# CAN-MPU.net
KiCad netlist of a schematic drawn in EAGLE
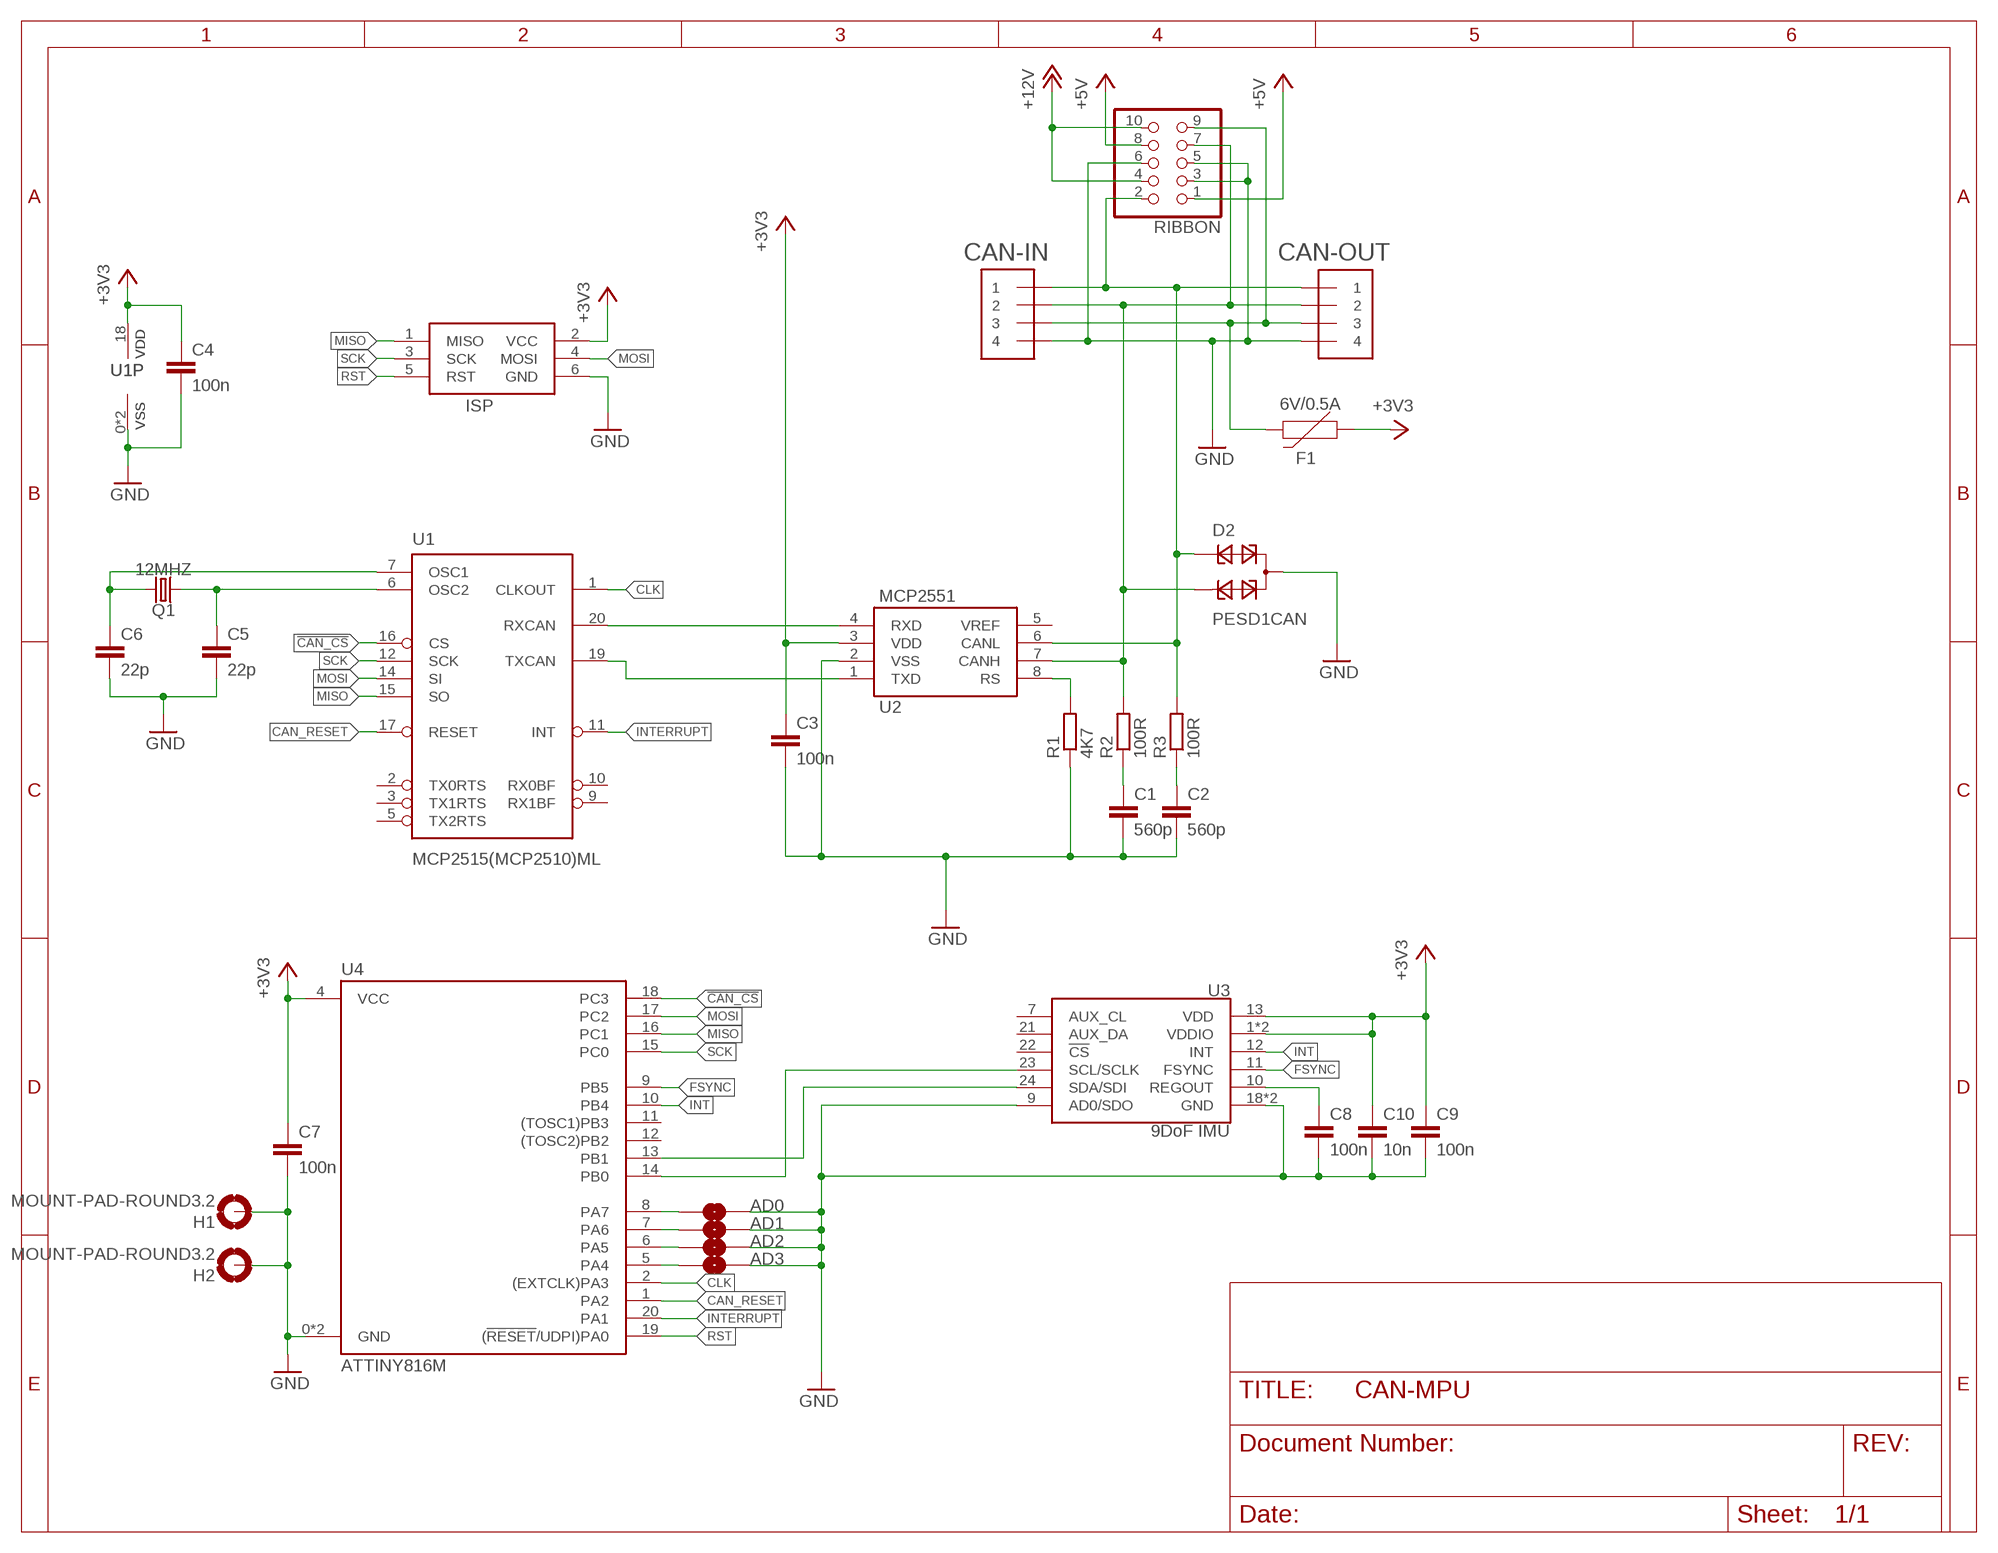
[diagram p0: schematic, sheet 1]

(export (version "E")
  (design (tool "Eeschema 10.0.6"))
  (components
    (comp (ref "AD0")
      (value "JUMPER-SMT_2_NO_SILK")
      (footprint "eagle-import:SMT-JUMPER_2_NO_SILK")
      (libsource (lib "eagle-import") (part "JUMPER-SMT_2_NO_SILK"))
    )
    (comp (ref "AD1")
      (value "JUMPER-SMT_2_NO_SILK")
      (footprint "eagle-import:SMT-JUMPER_2_NO_SILK")
      (libsource (lib "eagle-import") (part "JUMPER-SMT_2_NO_SILK"))
    )
    (comp (ref "AD2")
      (value "JUMPER-SMT_2_NO_SILK")
      (footprint "eagle-import:SMT-JUMPER_2_NO_SILK")
      (libsource (lib "eagle-import") (part "JUMPER-SMT_2_NO_SILK"))
    )
    (comp (ref "AD3")
      (value "JUMPER-SMT_2_NO_SILK")
      (footprint "eagle-import:SMT-JUMPER_2_NO_SILK")
      (libsource (lib "eagle-import") (part "JUMPER-SMT_2_NO_SILK"))
    )
    (comp (ref "C1")
      (value "560p")
      (footprint "eagle-import:C0603")
      (libsource (lib "eagle-import") (part "C-EUC0603"))
    )
    (comp (ref "C2")
      (value "560p")
      (footprint "eagle-import:C0603")
      (libsource (lib "eagle-import") (part "C-EUC0603"))
    )
    (comp (ref "C3")
      (value "100n")
      (footprint "eagle-import:C0603")
      (libsource (lib "eagle-import") (part "C-EUC0603"))
    )
    (comp (ref "C4")
      (value "100n")
      (footprint "eagle-import:C0603")
      (libsource (lib "eagle-import") (part "C-EUC0603"))
    )
    (comp (ref "C5")
      (value "22p")
      (footprint "eagle-import:C0603")
      (libsource (lib "eagle-import") (part "C-EUC0603"))
    )
    (comp (ref "C6")
      (value "22p")
      (footprint "eagle-import:C0603")
      (libsource (lib "eagle-import") (part "C-EUC0603"))
    )
    (comp (ref "C7")
      (value "100n")
      (footprint "eagle-import:C0603")
      (libsource (lib "eagle-import") (part "C-EUC0603"))
    )
    (comp (ref "C8")
      (value "100n")
      (footprint "eagle-import:C0603")
      (libsource (lib "eagle-import") (part "C-EUC0603"))
    )
    (comp (ref "C9")
      (value "100n")
      (footprint "eagle-import:C0603")
      (libsource (lib "eagle-import") (part "C-EUC0603"))
    )
    (comp (ref "C10")
      (value "10n")
      (footprint "eagle-import:C0603")
      (libsource (lib "eagle-import") (part "C-EUC0603"))
    )
    (comp (ref "CAN-IN")
      (value "STRAWSON_EAGLE_LIB_JST_SH_4")
      (footprint "eagle-import:STRAWSON_EAGLE_LIB_JST_SH_4_SMD")
      (libsource (lib "eagle-import") (part "STRAWSON_EAGLE_LIB_JST_SH_4"))
    )
    (comp (ref "CAN-OUT")
      (value "STRAWSON_EAGLE_LIB_JST_SH_4")
      (footprint "eagle-import:STRAWSON_EAGLE_LIB_JST_SH_4_SMD")
      (libsource (lib "eagle-import") (part "STRAWSON_EAGLE_LIB_JST_SH_4"))
    )
    (comp (ref "D2")
      (value "PESD1CAN")
      (footprint "eagle-import:SOT23")
      (libsource (lib "eagle-import") (part "PESD1CAN"))
    )
    (comp (ref "F1")
      (value "6V/0.5A")
      (footprint "eagle-import:1206")
      (libsource (lib "eagle-import") (part "PPTC_HALF-AMP"))
    )
    (comp (ref "H1")
      (value "MOUNT-PAD-ROUND3.2")
      (footprint "eagle-import:3,2-PAD")
      (libsource (lib "eagle-import") (part "MOUNT-PAD-ROUND3.2"))
    )
    (comp (ref "H2")
      (value "MOUNT-PAD-ROUND3.2")
      (footprint "eagle-import:3,2-PAD")
      (libsource (lib "eagle-import") (part "MOUNT-PAD-ROUND3.2"))
    )
    (comp (ref "ISP")
      (value "AVRISP-6")
      (footprint "eagle-import:AVRISP")
      (libsource (lib "eagle-import") (part "AVRISP-6"))
    )
    (comp (ref "Q1")
      (value "12MHZ")
      (footprint "eagle-import:CRYSTAL-SMD-3.2X1.5MM")
      (libsource (lib "eagle-import") (part "CRYSTALSMD-3.2X1.5"))
    )
    (comp (ref "R1")
      (value "4K7")
      (footprint "eagle-import:R0603")
      (libsource (lib "eagle-import") (part "R-EU_R0603"))
    )
    (comp (ref "R2")
      (value "100R")
      (footprint "eagle-import:R0603")
      (libsource (lib "eagle-import") (part "R-EU_R0603"))
    )
    (comp (ref "R3")
      (value "100R")
      (footprint "eagle-import:R0603")
      (libsource (lib "eagle-import") (part "R-EU_R0603"))
    )
    (comp (ref "RIBBON")
      (value "PINHD-2X5_2.54-SMD")
      (footprint "eagle-import:2X05SMD")
      (libsource (lib "eagle-import") (part "PINHD-2X5_2.54-SMD"))
    )
    (comp (ref "U1")
      (value "MCP2515(MCP2510)ML")
      (footprint "eagle-import:QFN20")
      (libsource (lib "eagle-import") (part "MCP2515(MCP2510)ML"))
    )
    (comp (ref "U2")
      (value "MCP2551")
      (footprint "eagle-import:SO08")
      (libsource (lib "eagle-import") (part "MCP2551"))
    )
    (comp (ref "U3")
      (value "9DoF IMU")
      (footprint "eagle-import:QFN24-3X3")
      (libsource (lib "eagle-import") (part "MPU-9250"))
    )
    (comp (ref "U4")
      (value "ATTINY816M")
      (footprint "eagle-import:QFN20")
      (libsource (lib "eagle-import") (part "ATTINY816M"))
    )
  )
  (nets
    (net (code "1") (name "+3V3") (class "Default")
      (node (ref "C10") (pin "1") (pinfunction "1_1") (pintype "passive"))
      (node (ref "C3") (pin "1") (pinfunction "1_1") (pintype "passive"))
      (node (ref "C4") (pin "1") (pinfunction "1_1") (pintype "passive"))
      (node (ref "C7") (pin "1") (pinfunction "1_1") (pintype "passive"))
      (node (ref "C9") (pin "1") (pinfunction "1_1") (pintype "passive"))
      (node (ref "F1") (pin "1") (pinfunction "1_1") (pintype "bidirectional"))
      (node (ref "ISP") (pin "2") (pinfunction "VCC_2") (pintype "power_in"))
      (node (ref "U1") (pin "18") (pinfunction "VDD_18") (pintype "power_in"))
      (node (ref "U2") (pin "3") (pinfunction "VDD_3") (pintype "bidirectional"))
      (node (ref "U3") (pin "1") (pinfunction "VDDIO_1") (pintype "bidirectional"))
      (node (ref "U3") (pin "13") (pinfunction "VDD_13") (pintype "bidirectional"))
      (node (ref "U3") (pin "8") (pinfunction "VDDIO_8") (pintype "bidirectional"))
      (node (ref "U4") (pin "4") (pinfunction "VCC_4") (pintype "bidirectional"))
    )
    (net (code "2") (name "+5V") (class "Default")
      (node (ref "RIBBON") (pin "1") (pinfunction "1_1") (pintype "passive"))
      (node (ref "RIBBON") (pin "8") (pinfunction "8_8") (pintype "passive"))
    )
    (net (code "3") (name "+12V") (class "Default")
      (node (ref "RIBBON") (pin "10") (pinfunction "10_10") (pintype "passive"))
      (node (ref "RIBBON") (pin "4") (pinfunction "4_4") (pintype "passive"))
    )
    (net (code "4") (name "/~{CAN_CS}") (class "Default")
      (node (ref "U1") (pin "16") (pinfunction "CS_16") (pintype "input"))
      (node (ref "U4") (pin "18") (pinfunction "PC3_18") (pintype "bidirectional"))
    )
    (net (code "5") (name "CAN_RESET") (class "Default")
      (node (ref "U1") (pin "17") (pinfunction "RESET_17") (pintype "input"))
      (node (ref "U4") (pin "1") (pinfunction "PA2_1") (pintype "bidirectional"))
    )
    (net (code "6") (name "CLK") (class "Default")
      (node (ref "U1") (pin "1") (pinfunction "CLKOUT_1") (pintype "output"))
      (node (ref "U4") (pin "2") (pinfunction "(EXTCLK)PA3_2") (pintype "bidirectional"))
    )
    (net (code "7") (name "FSYNC") (class "Default")
      (node (ref "U3") (pin "11") (pinfunction "FSYNC_11") (pintype "bidirectional"))
      (node (ref "U4") (pin "9") (pinfunction "PB5_9") (pintype "bidirectional"))
    )
    (net (code "8") (name "GND") (class "Default")
      (node (ref "AD0") (pin "2") (pinfunction "2_2") (pintype "passive"))
      (node (ref "AD1") (pin "2") (pinfunction "2_2") (pintype "passive"))
      (node (ref "AD2") (pin "2") (pinfunction "2_2") (pintype "passive"))
      (node (ref "AD3") (pin "2") (pinfunction "2_2") (pintype "passive"))
      (node (ref "C1") (pin "2") (pinfunction "2_2") (pintype "passive"))
      (node (ref "C10") (pin "2") (pinfunction "2_2") (pintype "passive"))
      (node (ref "C2") (pin "2") (pinfunction "2_2") (pintype "passive"))
      (node (ref "C3") (pin "2") (pinfunction "2_2") (pintype "passive"))
      (node (ref "C4") (pin "2") (pinfunction "2_2") (pintype "passive"))
      (node (ref "C5") (pin "2") (pinfunction "2_2") (pintype "passive"))
      (node (ref "C6") (pin "2") (pinfunction "2_2") (pintype "passive"))
      (node (ref "C7") (pin "2") (pinfunction "2_2") (pintype "passive"))
      (node (ref "C8") (pin "2") (pinfunction "2_2") (pintype "passive"))
      (node (ref "C9") (pin "2") (pinfunction "2_2") (pintype "passive"))
      (node (ref "CAN-IN") (pin "4") (pinfunction "4_4") (pintype "bidirectional"))
      (node (ref "CAN-OUT") (pin "4") (pinfunction "4_4") (pintype "bidirectional"))
      (node (ref "D2") (pin "3") (pinfunction "3_3") (pintype "passive"))
      (node (ref "H1") (pin "B3,2") (pinfunction "MOUNT_B3,2") (pintype "passive"))
      (node (ref "H2") (pin "B3,2") (pinfunction "MOUNT_B3,2") (pintype "passive"))
      (node (ref "ISP") (pin "6") (pinfunction "GND_6") (pintype "power_in"))
      (node (ref "R1") (pin "1") (pinfunction "1_1") (pintype "passive"))
      (node (ref "RIBBON") (pin "3") (pinfunction "3_3") (pintype "passive"))
      (node (ref "RIBBON") (pin "5") (pinfunction "5_5") (pintype "passive"))
      (node (ref "RIBBON") (pin "6") (pinfunction "6_6") (pintype "passive"))
      (node (ref "U1") (pin "0") (pinfunction "VSS_0") (pintype "power_in"))
      (node (ref "U1") (pin "8") (pinfunction "VSS_8") (pintype "power_in"))
      (node (ref "U2") (pin "2") (pinfunction "VSS_2") (pintype "bidirectional"))
      (node (ref "U3") (pin "18") (pinfunction "GND_18") (pintype "bidirectional"))
      (node (ref "U3") (pin "20") (pinfunction "GND_20") (pintype "bidirectional"))
      (node (ref "U3") (pin "9") (pinfunction "AD0/SDO_9") (pintype "bidirectional"))
      (node (ref "U4") (pin "0") (pinfunction "GND_0") (pintype "bidirectional"))
      (node (ref "U4") (pin "3") (pinfunction "GND_3") (pintype "bidirectional"))
    )
    (net (code "9") (name "INT") (class "Default")
      (node (ref "U3") (pin "12") (pinfunction "INT_12") (pintype "bidirectional"))
      (node (ref "U4") (pin "10") (pinfunction "PB4_10") (pintype "bidirectional"))
    )
    (net (code "10") (name "INTERRUPT") (class "Default")
      (node (ref "U1") (pin "11") (pinfunction "INT_11") (pintype "output"))
      (node (ref "U4") (pin "20") (pinfunction "PA1_20") (pintype "bidirectional"))
    )
    (net (code "11") (name "MISO") (class "Default")
      (node (ref "ISP") (pin "1") (pinfunction "MISO_1") (pintype "input"))
      (node (ref "U1") (pin "15") (pinfunction "SO_15") (pintype "output"))
      (node (ref "U4") (pin "16") (pinfunction "PC1_16") (pintype "bidirectional"))
    )
    (net (code "12") (name "MOSI") (class "Default")
      (node (ref "ISP") (pin "4") (pinfunction "MOSI_4") (pintype "output"))
      (node (ref "U1") (pin "14") (pinfunction "SI_14") (pintype "input"))
      (node (ref "U4") (pin "17") (pinfunction "PC2_17") (pintype "bidirectional"))
    )
    (net (code "13") (name "Net-(C1-Pad1)") (class "Default")
      (node (ref "C1") (pin "1") (pinfunction "1_1") (pintype "passive"))
      (node (ref "R2") (pin "1") (pinfunction "1_1") (pintype "passive"))
    )
    (net (code "14") (name "Net-(C2-Pad1)") (class "Default")
      (node (ref "C2") (pin "1") (pinfunction "1_1") (pintype "passive"))
      (node (ref "R3") (pin "1") (pinfunction "1_1") (pintype "passive"))
    )
    (net (code "15") (name "Net-(CAN-IN-Pad3)") (class "Default")
      (node (ref "CAN-IN") (pin "3") (pinfunction "3_3") (pintype "bidirectional"))
      (node (ref "CAN-OUT") (pin "3") (pinfunction "3_3") (pintype "bidirectional"))
      (node (ref "F1") (pin "2") (pinfunction "2_2") (pintype "bidirectional"))
      (node (ref "RIBBON") (pin "9") (pinfunction "9_9") (pintype "passive"))
    )
    (net (code "16") (name "Net-(Q1-1)") (class "Default")
      (node (ref "C5") (pin "1") (pinfunction "1_1") (pintype "passive"))
      (node (ref "Q1") (pin "P$1") (pinfunction "1_P$1") (pintype "passive"))
      (node (ref "U1") (pin "6") (pinfunction "OSC2_6") (pintype "output"))
    )
    (net (code "17") (name "Net-(Q1-2)") (class "Default")
      (node (ref "C6") (pin "1") (pinfunction "1_1") (pintype "passive"))
      (node (ref "Q1") (pin "P$2") (pinfunction "2_P$2") (pintype "passive"))
      (node (ref "U1") (pin "7") (pinfunction "OSC1_7") (pintype "input"))
    )
    (net (code "18") (name "Net-(U1A-RXCAN)") (class "Default")
      (node (ref "U1") (pin "20") (pinfunction "RXCAN_20") (pintype "input"))
      (node (ref "U2") (pin "4") (pinfunction "RXD_4") (pintype "bidirectional"))
    )
    (net (code "19") (name "Net-(U1A-TXCAN)") (class "Default")
      (node (ref "U1") (pin "19") (pinfunction "TXCAN_19") (pintype "output"))
      (node (ref "U2") (pin "1") (pinfunction "TXD_1") (pintype "bidirectional"))
    )
    (net (code "20") (name "Net-(U2-CANH)") (class "Default")
      (node (ref "CAN-IN") (pin "2") (pinfunction "2_2") (pintype "bidirectional"))
      (node (ref "CAN-OUT") (pin "2") (pinfunction "2_2") (pintype "bidirectional"))
      (node (ref "D2") (pin "2") (pinfunction "2_2") (pintype "passive"))
      (node (ref "R2") (pin "2") (pinfunction "2_2") (pintype "passive"))
      (node (ref "RIBBON") (pin "7") (pinfunction "7_7") (pintype "passive"))
      (node (ref "U2") (pin "7") (pinfunction "CANH_7") (pintype "bidirectional"))
    )
    (net (code "21") (name "Net-(U2-CANL)") (class "Default")
      (node (ref "CAN-IN") (pin "1") (pinfunction "1_1") (pintype "bidirectional"))
      (node (ref "CAN-OUT") (pin "1") (pinfunction "1_1") (pintype "bidirectional"))
      (node (ref "D2") (pin "1") (pinfunction "1_1") (pintype "passive"))
      (node (ref "R3") (pin "2") (pinfunction "2_2") (pintype "passive"))
      (node (ref "RIBBON") (pin "2") (pinfunction "2_2") (pintype "passive"))
      (node (ref "U2") (pin "6") (pinfunction "CANL_6") (pintype "bidirectional"))
    )
    (net (code "22") (name "Net-(U2-RS)") (class "Default")
      (node (ref "R1") (pin "2") (pinfunction "2_2") (pintype "passive"))
      (node (ref "U2") (pin "8") (pinfunction "RS_8") (pintype "bidirectional"))
    )
    (net (code "23") (name "Net-(U3-REGOUT)") (class "Default")
      (node (ref "C8") (pin "1") (pinfunction "1_1") (pintype "passive"))
      (node (ref "U3") (pin "10") (pinfunction "REGOUT_10") (pintype "bidirectional"))
    )
    (net (code "24") (name "Net-(U3-SCL{slash}SCLK)") (class "Default")
      (node (ref "U3") (pin "23") (pinfunction "SCL/SCLK_23") (pintype "bidirectional"))
      (node (ref "U4") (pin "14") (pinfunction "PB0_14") (pintype "bidirectional"))
    )
    (net (code "25") (name "Net-(U3-SDA{slash}SDI)") (class "Default")
      (node (ref "U3") (pin "24") (pinfunction "SDA/SDI_24") (pintype "bidirectional"))
      (node (ref "U4") (pin "13") (pinfunction "PB1_13") (pintype "bidirectional"))
    )
    (net (code "26") (name "Net-(U4-PA4)") (class "Default")
      (node (ref "AD3") (pin "1") (pinfunction "1_1") (pintype "passive"))
      (node (ref "U4") (pin "5") (pinfunction "PA4_5") (pintype "bidirectional"))
    )
    (net (code "27") (name "Net-(U4-PA5)") (class "Default")
      (node (ref "AD2") (pin "1") (pinfunction "1_1") (pintype "passive"))
      (node (ref "U4") (pin "6") (pinfunction "PA5_6") (pintype "bidirectional"))
    )
    (net (code "28") (name "Net-(U4-PA6)") (class "Default")
      (node (ref "AD1") (pin "1") (pinfunction "1_1") (pintype "passive"))
      (node (ref "U4") (pin "7") (pinfunction "PA6_7") (pintype "bidirectional"))
    )
    (net (code "29") (name "Net-(U4-PA7)") (class "Default")
      (node (ref "AD0") (pin "1") (pinfunction "1_1") (pintype "passive"))
      (node (ref "U4") (pin "8") (pinfunction "PA7_8") (pintype "bidirectional"))
    )
    (net (code "30") (name "RST") (class "Default")
      (node (ref "ISP") (pin "5") (pinfunction "RST_5") (pintype "output"))
      (node (ref "U4") (pin "19") (pinfunction "(~{RESET}/UDPI)PA0_19") (pintype "bidirectional"))
    )
    (net (code "31") (name "SCK") (class "Default")
      (node (ref "ISP") (pin "3") (pinfunction "SCK_3") (pintype "output"))
      (node (ref "U1") (pin "12") (pinfunction "SCK_12") (pintype "input"))
      (node (ref "U4") (pin "15") (pinfunction "PC0_15") (pintype "bidirectional"))
    )
    (net (code "32") (name "unconnected-(U1A-RX0BF-Pad10)") (class "Default")
      (node (ref "U1") (pin "10") (pinfunction "RX0BF_10") (pintype "output"))
    )
    (net (code "33") (name "unconnected-(U1A-RX1BF-Pad9)") (class "Default")
      (node (ref "U1") (pin "9") (pinfunction "RX1BF_9") (pintype "output"))
    )
    (net (code "34") (name "unconnected-(U1A-TX0RTS-Pad2)") (class "Default")
      (node (ref "U1") (pin "2") (pinfunction "TX0RTS_2") (pintype "input"))
    )
    (net (code "35") (name "unconnected-(U1A-TX1RTS-Pad3)") (class "Default")
      (node (ref "U1") (pin "3") (pinfunction "TX1RTS_3") (pintype "input"))
    )
    (net (code "36") (name "unconnected-(U1A-TX2RTS-Pad5)") (class "Default")
      (node (ref "U1") (pin "5") (pinfunction "TX2RTS_5") (pintype "input"))
    )
    (net (code "37") (name "unconnected-(U2-VREF-Pad5)") (class "Default")
      (node (ref "U2") (pin "5") (pinfunction "VREF_5") (pintype "bidirectional"))
    )
    (net (code "38") (name "unconnected-(U3-AUX_CL-Pad7)") (class "Default")
      (node (ref "U3") (pin "7") (pinfunction "AUX_CL_7") (pintype "bidirectional"))
    )
    (net (code "39") (name "unconnected-(U3-AUX_DA-Pad21)") (class "Default")
      (node (ref "U3") (pin "21") (pinfunction "AUX_DA_21") (pintype "bidirectional"))
    )
    (net (code "40") (name "unconnected-(U3-~{CS}-Pad22)") (class "Default")
      (node (ref "U3") (pin "22") (pinfunction "~{CS}_22") (pintype "bidirectional"))
    )
    (net (code "41") (name "unconnected-(U4-(TOSC1)PB3-Pad11)") (class "Default")
      (node (ref "U4") (pin "11") (pinfunction "(TOSC1)PB3_11") (pintype "bidirectional"))
    )
    (net (code "42") (name "unconnected-(U4-(TOSC2)PB2-Pad12)") (class "Default")
      (node (ref "U4") (pin "12") (pinfunction "(TOSC2)PB2_12") (pintype "bidirectional"))
    )
  )
)
